# raspberry_interface.net
KiCad netlist of a schematic drawn in Altium Designer
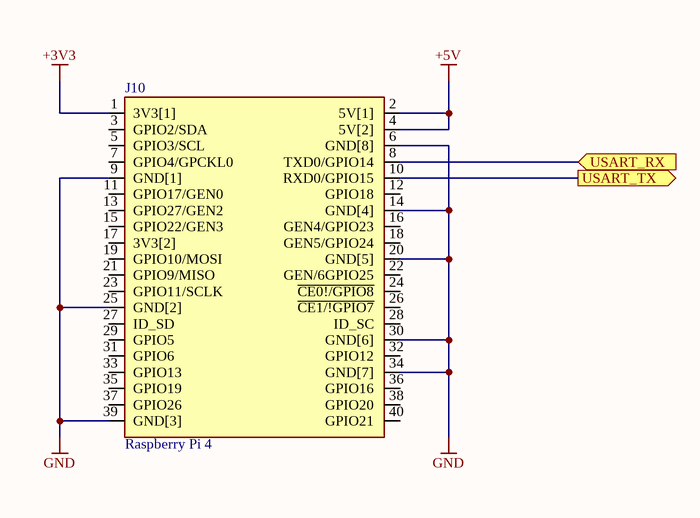
[diagram p0: raspberry_interface.SchDoc]

(export (version "E")
  (design (tool "Eeschema 10.0.6"))
  (components
    (comp (ref "J10")
      (value "Raspberry Pi 4")
      (footprint "40P_HEADER")
      (description "Raspberry Pi 4 with Headers_")
      (fields (field (name "MP") "ADA3708") (field (name "MF") "Raspberry Pi"))
      (libsource (lib "Schlib") (part "RASPBERRY_PI4"))
    )
  )
  (nets
    (net (code "1") (name "+3V3") (class "Default")
      (node (ref "J10") (pin "1") (pinfunction "3V3[1]_1") (pintype "power_in"))
    )
    (net (code "2") (name "+5V") (class "Default")
      (node (ref "J10") (pin "2") (pinfunction "5V[1]_2") (pintype "power_in"))
      (node (ref "J10") (pin "4") (pinfunction "5V[2]_4") (pintype "power_in"))
    )
    (net (code "3") (name "/USART_RX") (class "Default")
      (node (ref "J10") (pin "8") (pinfunction "TXD0/GPIO14_8") (pintype "bidirectional"))
    )
    (net (code "4") (name "/USART_TX") (class "Default")
      (node (ref "J10") (pin "10") (pinfunction "RXD0/GPIO15_10") (pintype "bidirectional"))
    )
    (net (code "5") (name "GND") (class "Default")
      (node (ref "J10") (pin "14") (pinfunction "GND[4]_14") (pintype "power_in"))
      (node (ref "J10") (pin "20") (pinfunction "GND[5]_20") (pintype "power_in"))
      (node (ref "J10") (pin "25") (pinfunction "GND[2]_25") (pintype "power_in"))
      (node (ref "J10") (pin "30") (pinfunction "GND[6]_30") (pintype "power_in"))
      (node (ref "J10") (pin "34") (pinfunction "GND[7]_34") (pintype "power_in"))
      (node (ref "J10") (pin "39") (pinfunction "GND[3]_39") (pintype "power_in"))
      (node (ref "J10") (pin "6") (pinfunction "GND[8]_6") (pintype "power_in"))
      (node (ref "J10") (pin "9") (pinfunction "GND[1]_9") (pintype "power_in"))
    )
    (net (code "6") (name "unconnected-(J10-3V3[2]-Pad17)") (class "Default")
      (node (ref "J10") (pin "17") (pinfunction "3V3[2]_17") (pintype "power_in"))
    )
    (net (code "7") (name "unconnected-(J10-GEN4{slash}GPIO23-Pad16)") (class "Default")
      (node (ref "J10") (pin "16") (pinfunction "GEN4/GPIO23_16") (pintype "bidirectional"))
    )
    (net (code "8") (name "unconnected-(J10-GEN5{slash}GPIO24-Pad18)") (class "Default")
      (node (ref "J10") (pin "18") (pinfunction "GEN5/GPIO24_18") (pintype "bidirectional"))
    )
    (net (code "9") (name "unconnected-(J10-GEN{slash}6GPIO25-Pad22)") (class "Default")
      (node (ref "J10") (pin "22") (pinfunction "GEN/6GPIO25_22") (pintype "bidirectional"))
    )
    (net (code "10") (name "unconnected-(J10-GPIO2{slash}SDA-Pad3)") (class "Default")
      (node (ref "J10") (pin "3") (pinfunction "GPIO2/SDA_3") (pintype "bidirectional"))
    )
    (net (code "11") (name "unconnected-(J10-GPIO3{slash}SCL-Pad5)") (class "Default")
      (node (ref "J10") (pin "5") (pinfunction "GPIO3/SCL_5") (pintype "bidirectional"))
    )
    (net (code "12") (name "unconnected-(J10-GPIO4{slash}GPCKL0-Pad7)") (class "Default")
      (node (ref "J10") (pin "7") (pinfunction "GPIO4/GPCKL0_7") (pintype "bidirectional"))
    )
    (net (code "13") (name "unconnected-(J10-GPIO5-Pad29)") (class "Default")
      (node (ref "J10") (pin "29") (pinfunction "GPIO5_29") (pintype "bidirectional"))
    )
    (net (code "14") (name "unconnected-(J10-GPIO6-Pad31)") (class "Default")
      (node (ref "J10") (pin "31") (pinfunction "GPIO6_31") (pintype "bidirectional"))
    )
    (net (code "15") (name "unconnected-(J10-GPIO9{slash}MISO-Pad21)") (class "Default")
      (node (ref "J10") (pin "21") (pinfunction "GPIO9/MISO_21") (pintype "bidirectional"))
    )
    (net (code "16") (name "unconnected-(J10-GPIO10{slash}MOSI-Pad19)") (class "Default")
      (node (ref "J10") (pin "19") (pinfunction "GPIO10/MOSI_19") (pintype "bidirectional"))
    )
    (net (code "17") (name "unconnected-(J10-GPIO11{slash}SCLK-Pad23)") (class "Default")
      (node (ref "J10") (pin "23") (pinfunction "GPIO11/SCLK_23") (pintype "bidirectional"))
    )
    (net (code "18") (name "unconnected-(J10-GPIO12-Pad32)") (class "Default")
      (node (ref "J10") (pin "32") (pinfunction "GPIO12_32") (pintype "bidirectional"))
    )
    (net (code "19") (name "unconnected-(J10-GPIO13-Pad33)") (class "Default")
      (node (ref "J10") (pin "33") (pinfunction "GPIO13_33") (pintype "bidirectional"))
    )
    (net (code "20") (name "unconnected-(J10-GPIO16-Pad36)") (class "Default")
      (node (ref "J10") (pin "36") (pinfunction "GPIO16_36") (pintype "bidirectional"))
    )
    (net (code "21") (name "unconnected-(J10-GPIO17{slash}GEN0-Pad11)") (class "Default")
      (node (ref "J10") (pin "11") (pinfunction "GPIO17/GEN0_11") (pintype "bidirectional"))
    )
    (net (code "22") (name "unconnected-(J10-GPIO18-Pad12)") (class "Default")
      (node (ref "J10") (pin "12") (pinfunction "GPIO18_12") (pintype "bidirectional"))
    )
    (net (code "23") (name "unconnected-(J10-GPIO19-Pad35)") (class "Default")
      (node (ref "J10") (pin "35") (pinfunction "GPIO19_35") (pintype "bidirectional"))
    )
    (net (code "24") (name "unconnected-(J10-GPIO20-Pad38)") (class "Default")
      (node (ref "J10") (pin "38") (pinfunction "GPIO20_38") (pintype "bidirectional"))
    )
    (net (code "25") (name "unconnected-(J10-GPIO21-Pad40)") (class "Default")
      (node (ref "J10") (pin "40") (pinfunction "GPIO21_40") (pintype "bidirectional"))
    )
    (net (code "26") (name "unconnected-(J10-GPIO22{slash}GEN3-Pad15)") (class "Default")
      (node (ref "J10") (pin "15") (pinfunction "GPIO22/GEN3_15") (pintype "bidirectional"))
    )
    (net (code "27") (name "unconnected-(J10-GPIO26-Pad37)") (class "Default")
      (node (ref "J10") (pin "37") (pinfunction "GPIO26_37") (pintype "bidirectional"))
    )
    (net (code "28") (name "unconnected-(J10-GPIO27{slash}GEN2-Pad13)") (class "Default")
      (node (ref "J10") (pin "13") (pinfunction "GPIO27/GEN2_13") (pintype "bidirectional"))
    )
    (net (code "29") (name "unconnected-(J10-ID_SC-Pad28)") (class "Default")
      (node (ref "J10") (pin "28") (pinfunction "ID_SC_28") (pintype "bidirectional"))
    )
    (net (code "30") (name "unconnected-(J10-ID_SD-Pad27)") (class "Default")
      (node (ref "J10") (pin "27") (pinfunction "ID_SD_27") (pintype "bidirectional"))
    )
    (net (code "31") (name "unconnected-(J10-~{CE0!{slash}GPIO8}-Pad24)") (class "Default")
      (node (ref "J10") (pin "24") (pinfunction "~{CE0!/GPIO8}_24") (pintype "bidirectional"))
    )
    (net (code "32") (name "unconnected-(J10-~{CE1{slash}!GPIO7}-Pad26)") (class "Default")
      (node (ref "J10") (pin "26") (pinfunction "~{CE1/!GPIO7}_26") (pintype "bidirectional"))
    )
  )
)
